# H2OhNo.net
KiCad netlist of a schematic drawn in EAGLE
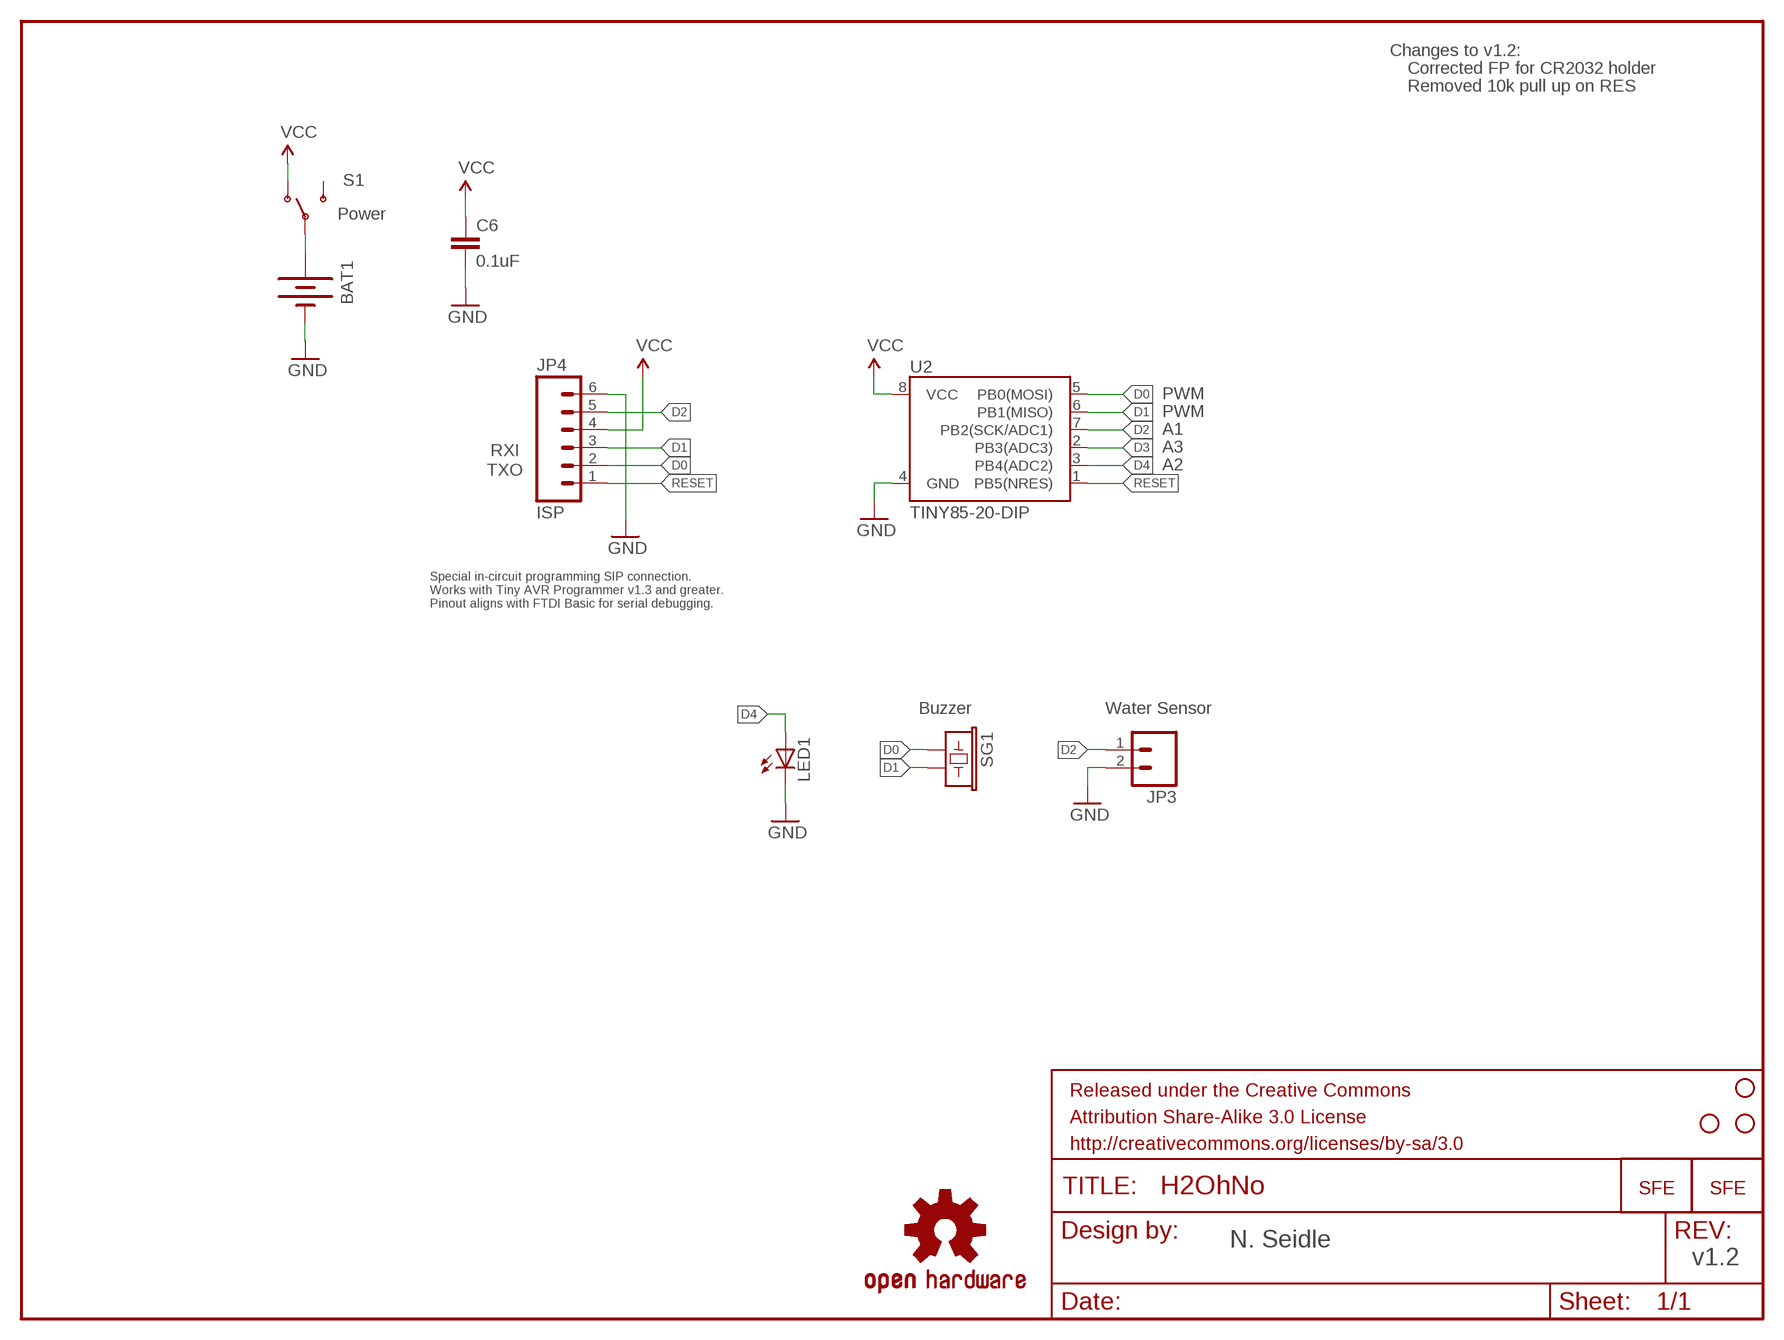
[diagram p0: schematic, sheet 1]

(export (version "E")
  (design (tool "Eeschema 10.0.6"))
  (components
    (comp (ref "BAT1")
      (value "BATTERY20PTH")
      (footprint "eagle-import:BATTCOM_20MM_PTH")
      (libsource (lib "eagle-import") (part "BATTERY20PTH"))
    )
    (comp (ref "C6")
      (value "0.1uF")
      (footprint "eagle-import:CAP-PTH-SMALL2")
      (libsource (lib "eagle-import") (part "CAPPTH2"))
    )
    (comp (ref "FRAME2")
      (value "FRAME-LETTER")
      (footprint "eagle-import:CREATIVE_COMMONS")
      (libsource (lib "eagle-import") (part "FRAME-LETTER"))
    )
    (comp (ref "JP3")
      (value "Water Sensor")
      (footprint "eagle-import:1X02")
      (libsource (lib "eagle-import") (part "M02PTH"))
    )
    (comp (ref "JP4")
      (value "ISP")
      (footprint "eagle-import:1X06")
      (libsource (lib "eagle-import") (part "M06SIP"))
    )
    (comp (ref "LED1")
      (value "LED5MM")
      (footprint "eagle-import:LED5MM")
      (libsource (lib "eagle-import") (part "LED5MM"))
    )
    (comp (ref "S1")
      (value "Power")
      (footprint "eagle-import:SWITCH-SPDT")
      (libsource (lib "eagle-import") (part "SWITCH-SPDTPTH"))
    )
    (comp (ref "SG1")
      (value "Buzzer")
      (footprint "eagle-import:BUZZER-12MM")
      (libsource (lib "eagle-import") (part "BUZZERPTH"))
    )
    (comp (ref "STANDOFF1")
      (value "STAND-OFF")
      (footprint "eagle-import:STAND-OFF")
      (libsource (lib "eagle-import") (part "STAND-OFF"))
    )
    (comp (ref "STANDOFF3")
      (value "STAND-OFF")
      (footprint "eagle-import:STAND-OFF")
      (libsource (lib "eagle-import") (part "STAND-OFF"))
    )
    (comp (ref "STANDOFF4")
      (value "STAND-OFF")
      (footprint "eagle-import:STAND-OFF")
      (libsource (lib "eagle-import") (part "STAND-OFF"))
    )
    (comp (ref "U$1")
      (value "LOGO-SFESK")
      (footprint "eagle-import:SFE-LOGO-FLAME")
      (libsource (lib "eagle-import") (part "LOGO-SFESK"))
    )
    (comp (ref "U$4")
      (value "OSHW-LOGOS")
      (footprint "eagle-import:OSHW-LOGO-S")
      (libsource (lib "eagle-import") (part "OSHW-LOGOS"))
    )
    (comp (ref "U$5")
      (value "LOGO-SFENW2")
      (footprint "eagle-import:SFE-NEW-WEB")
      (libsource (lib "eagle-import") (part "LOGO-SFENW2"))
    )
    (comp (ref "U2")
      (value "TINY85-20-DIP")
      (footprint "eagle-import:DIP08")
      (fields (field (name "PROD_ID") "IC-09445"))
      (libsource (lib "eagle-import") (part "ATTINY45TINY85-20-DIP"))
    )
  )
  (nets
    (net (code "1") (name "D0") (class "Default")
      (node (ref "JP4") (pin "2") (pinfunction "2_2") (pintype "passive"))
      (node (ref "SG1") (pin "+") (pinfunction "1_+") (pintype "passive"))
      (node (ref "U2") (pin "5") (pinfunction "PB0(MOSI)_5") (pintype "bidirectional"))
    )
    (net (code "2") (name "D1") (class "Default")
      (node (ref "JP4") (pin "3") (pinfunction "3_3") (pintype "passive"))
      (node (ref "SG1") (pin "-") (pinfunction "2_-") (pintype "passive"))
      (node (ref "U2") (pin "6") (pinfunction "PB1(MISO)_6") (pintype "bidirectional"))
    )
    (net (code "3") (name "D2") (class "Default")
      (node (ref "JP3") (pin "1") (pinfunction "1_1") (pintype "passive"))
      (node (ref "JP4") (pin "5") (pinfunction "5_5") (pintype "passive"))
      (node (ref "U2") (pin "7") (pinfunction "PB2(SCK/ADC1)_7") (pintype "bidirectional"))
    )
    (net (code "4") (name "D3") (class "Default")
      (node (ref "U2") (pin "2") (pinfunction "PB3(ADC3)_2") (pintype "bidirectional"))
    )
    (net (code "5") (name "D4") (class "Default")
      (node (ref "LED1") (pin "A") (pinfunction "A_A") (pintype "passive"))
      (node (ref "U2") (pin "3") (pinfunction "PB4(ADC2)_3") (pintype "bidirectional"))
    )
    (net (code "6") (name "GND") (class "Default")
      (node (ref "BAT1") (pin "2") (pinfunction "-_2") (pintype "power_in"))
      (node (ref "C6") (pin "2") (pinfunction "2_2") (pintype "passive"))
      (node (ref "JP3") (pin "2") (pinfunction "2_2") (pintype "passive"))
      (node (ref "JP4") (pin "6") (pinfunction "6_6") (pintype "passive"))
      (node (ref "LED1") (pin "K") (pinfunction "C_K") (pintype "passive"))
      (node (ref "U2") (pin "4") (pinfunction "GND_4") (pintype "bidirectional"))
    )
    (net (code "7") (name "Net-(BAT1-+)") (class "Default")
      (node (ref "BAT1") (pin "1") (pinfunction "+_1") (pintype "power_in"))
      (node (ref "S1") (pin "2") (pinfunction "P_2") (pintype "passive"))
    )
    (net (code "8") (name "RESET") (class "Default")
      (node (ref "JP4") (pin "1") (pinfunction "1_1") (pintype "passive"))
      (node (ref "U2") (pin "1") (pinfunction "PB5(NRES)_1") (pintype "bidirectional"))
    )
    (net (code "9") (name "VCC") (class "Default")
      (node (ref "C6") (pin "1") (pinfunction "1_1") (pintype "passive"))
      (node (ref "JP4") (pin "4") (pinfunction "4_4") (pintype "passive"))
      (node (ref "S1") (pin "1") (pinfunction "O_1") (pintype "passive"))
      (node (ref "U2") (pin "8") (pinfunction "VCC_8") (pintype "bidirectional"))
    )
    (net (code "10") (name "unconnected-(S1-S-Pad3)") (class "Default")
      (node (ref "S1") (pin "3") (pinfunction "S_3") (pintype "passive"))
    )
  )
)
